# carlos_lm3886.net
KiCad netlist of a schematic drawn in EAGLE
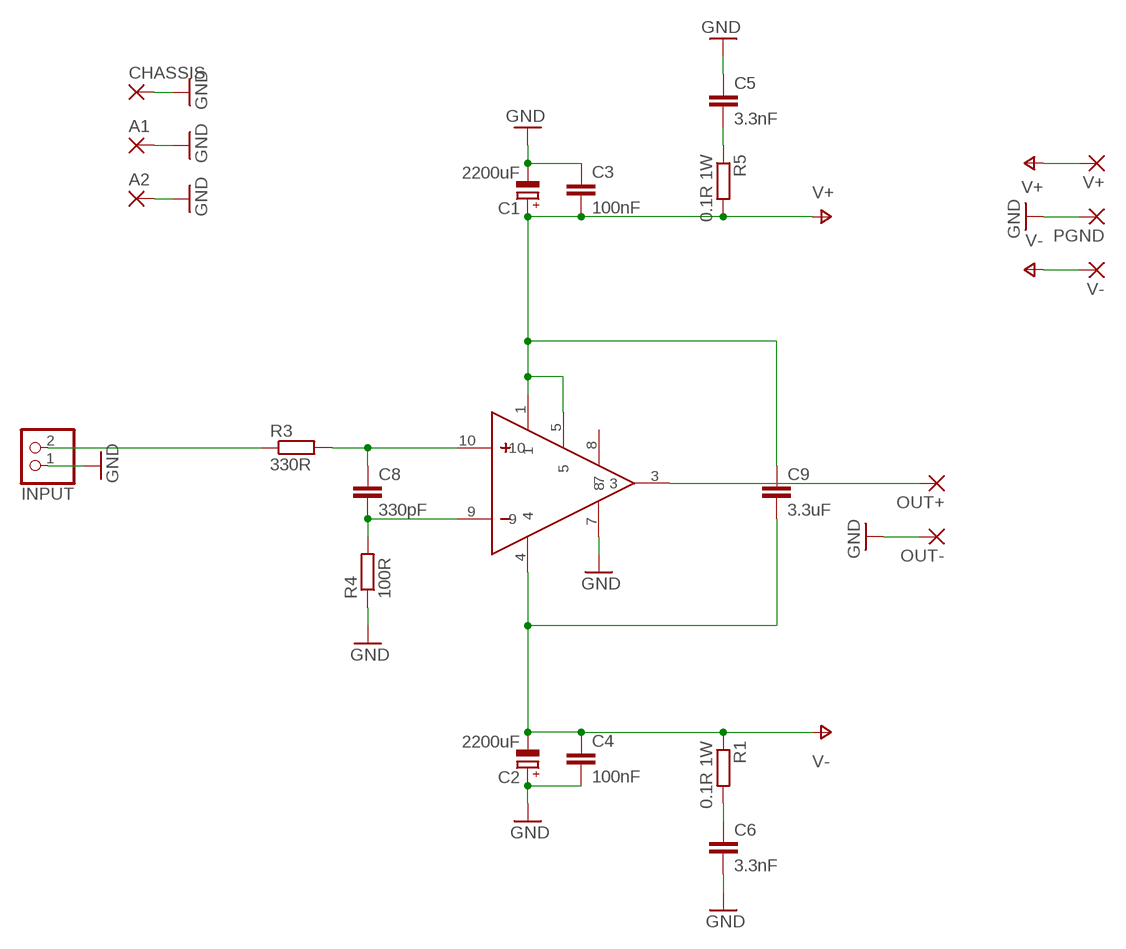
[diagram p0: schematic, sheet 1]

(export (version "E")
  (design (tool "Eeschema 10.0.6"))
  (components
    (comp (ref "A1")
      (value "2,54/1,0")
      (footprint "eagle-import:2,54_1,0")
      (libsource (lib "eagle-import") (part "2,54/1,0"))
    )
    (comp (ref "A2")
      (value "2,54/1,0")
      (footprint "eagle-import:2,54_1,0")
      (libsource (lib "eagle-import") (part "2,54/1,0"))
    )
    (comp (ref "C1")
      (value "2200uF")
      (footprint "eagle-import:E7,5-18")
      (libsource (lib "eagle-import") (part "CPOL-EUE7.5-18"))
    )
    (comp (ref "C2")
      (value "2200uF")
      (footprint "eagle-import:E7,5-18")
      (libsource (lib "eagle-import") (part "CPOL-EUE7.5-18"))
    )
    (comp (ref "C3")
      (value "100nF")
      (footprint "eagle-import:C150-054X183")
      (libsource (lib "eagle-import") (part "C-EU150-054X183"))
    )
    (comp (ref "C4")
      (value "100nF")
      (footprint "eagle-import:C150-054X183")
      (libsource (lib "eagle-import") (part "C-EU150-054X183"))
    )
    (comp (ref "C5")
      (value "3.3nF")
      (footprint "eagle-import:C075-032X103")
      (libsource (lib "eagle-import") (part "C-EU075-032X103"))
    )
    (comp (ref "C6")
      (value "3.3nF")
      (footprint "eagle-import:C075-032X103")
      (libsource (lib "eagle-import") (part "C-EU075-032X103"))
    )
    (comp (ref "C8")
      (value "330pF")
      (footprint "eagle-import:C050-045X075")
      (libsource (lib "eagle-import") (part "C-EU050-045X075"))
    )
    (comp (ref "C9")
      (value "3.3uF")
      (footprint "eagle-import:C225-087X268")
      (libsource (lib "eagle-import") (part "C-EU225-087X268"))
    )
    (comp (ref "CHASSIS")
      (value "2,54/1,0")
      (footprint "eagle-import:2,54_1,0")
      (libsource (lib "eagle-import") (part "2,54/1,0"))
    )
    (comp (ref "INPUT")
      (value "PINHD-1X2")
      (footprint "eagle-import:1X02")
      (libsource (lib "eagle-import") (part "PINHD-1X2"))
    )
    (comp (ref "OUT+")
      (value "2,54/1,0")
      (footprint "eagle-import:2,54_1,0")
      (libsource (lib "eagle-import") (part "2,54/1,0"))
    )
    (comp (ref "OUT-")
      (value "2,54/1,0")
      (footprint "eagle-import:2,54_1,0")
      (libsource (lib "eagle-import") (part "2,54/1,0"))
    )
    (comp (ref "PGND")
      (value "2,54/1,0")
      (footprint "eagle-import:2,54_1,0")
      (libsource (lib "eagle-import") (part "2,54/1,0"))
    )
    (comp (ref "R1")
      (value "0.1R 1W")
      (footprint "eagle-import:0309_10")
      (libsource (lib "eagle-import") (part "resistor_R-EU_0309/10"))
    )
    (comp (ref "R3")
      (value "330R")
      (footprint "eagle-import:0207_10")
      (libsource (lib "eagle-import") (part "R-EU_0207/10"))
    )
    (comp (ref "R4")
      (value "100R")
      (footprint "eagle-import:0207_10")
      (libsource (lib "eagle-import") (part "R-EU_0207/10"))
    )
    (comp (ref "R5")
      (value "0.1R 1W")
      (footprint "eagle-import:0309_10")
      (libsource (lib "eagle-import") (part "resistor_R-EU_0309/10"))
    )
    (comp (ref "U$1")
      (value "LM3886T")
      (footprint "eagle-import:TO220-11")
      (libsource (lib "eagle-import") (part "LM3886T"))
    )
    (comp (ref "V+")
      (value "2,54/1,0")
      (footprint "eagle-import:2,54_1,0")
      (libsource (lib "eagle-import") (part "2,54/1,0"))
    )
    (comp (ref "V-")
      (value "2,54/1,0")
      (footprint "eagle-import:2,54_1,0")
      (libsource (lib "eagle-import") (part "2,54/1,0"))
    )
  )
  (nets
    (net (code "1") (name "GND") (class "Default")
      (node (ref "A1") (pin "1") (pinfunction "P_1") (pintype "passive"))
      (node (ref "A2") (pin "1") (pinfunction "P_1") (pintype "passive"))
      (node (ref "C1") (pin "-") (pinfunction "-_-") (pintype "passive"))
      (node (ref "C2") (pin "+") (pinfunction "+_+") (pintype "passive"))
      (node (ref "C3") (pin "1") (pinfunction "1_1") (pintype "passive"))
      (node (ref "C4") (pin "2") (pinfunction "2_2") (pintype "passive"))
      (node (ref "C5") (pin "1") (pinfunction "1_1") (pintype "passive"))
      (node (ref "C6") (pin "2") (pinfunction "2_2") (pintype "passive"))
      (node (ref "CHASSIS") (pin "1") (pinfunction "P_1") (pintype "passive"))
      (node (ref "INPUT") (pin "1") (pinfunction "1_1") (pintype "passive"))
      (node (ref "OUT-") (pin "1") (pinfunction "P_1") (pintype "passive"))
      (node (ref "PGND") (pin "1") (pinfunction "P_1") (pintype "passive"))
      (node (ref "R4") (pin "1") (pinfunction "1_1") (pintype "passive"))
      (node (ref "U$1") (pin "7") (pinfunction "7_7") (pintype "power_in"))
    )
    (net (code "2") (name "Net-(C5-Pad2)") (class "Default")
      (node (ref "C5") (pin "2") (pinfunction "2_2") (pintype "passive"))
      (node (ref "R5") (pin "1") (pinfunction "1_1") (pintype "passive"))
    )
    (net (code "3") (name "Net-(C6-Pad1)") (class "Default")
      (node (ref "C6") (pin "1") (pinfunction "1_1") (pintype "passive"))
      (node (ref "R1") (pin "2") (pinfunction "2_2") (pintype "passive"))
    )
    (net (code "4") (name "Net-(C8-Pad1)") (class "Default")
      (node (ref "C8") (pin "1") (pinfunction "1_1") (pintype "passive"))
      (node (ref "R3") (pin "2") (pinfunction "2_2") (pintype "passive"))
      (node (ref "U$1") (pin "10") (pinfunction "10_10") (pintype "input"))
    )
    (net (code "5") (name "Net-(C8-Pad2)") (class "Default")
      (node (ref "C8") (pin "2") (pinfunction "2_2") (pintype "passive"))
      (node (ref "R4") (pin "2") (pinfunction "2_2") (pintype "passive"))
      (node (ref "U$1") (pin "9") (pinfunction "9_9") (pintype "input"))
    )
    (net (code "6") (name "Net-(INPUT-Pad2)") (class "Default")
      (node (ref "INPUT") (pin "2") (pinfunction "2_2") (pintype "passive"))
      (node (ref "R3") (pin "1") (pinfunction "1_1") (pintype "passive"))
    )
    (net (code "7") (name "Net-(OUT+-P)") (class "Default")
      (node (ref "OUT+") (pin "1") (pinfunction "P_1") (pintype "passive"))
      (node (ref "U$1") (pin "3") (pinfunction "3_3") (pintype "output"))
    )
    (net (code "8") (name "V+") (class "Default")
      (node (ref "C1") (pin "+") (pinfunction "+_+") (pintype "passive"))
      (node (ref "C3") (pin "2") (pinfunction "2_2") (pintype "passive"))
      (node (ref "C9") (pin "1") (pinfunction "1_1") (pintype "passive"))
      (node (ref "R5") (pin "2") (pinfunction "2_2") (pintype "passive"))
      (node (ref "U$1") (pin "1") (pinfunction "1_1") (pintype "power_in"))
      (node (ref "U$1") (pin "5") (pinfunction "5_5") (pintype "power_in"))
      (node (ref "V+") (pin "1") (pinfunction "P_1") (pintype "passive"))
    )
    (net (code "9") (name "V-") (class "Default")
      (node (ref "C2") (pin "-") (pinfunction "-_-") (pintype "passive"))
      (node (ref "C4") (pin "1") (pinfunction "1_1") (pintype "passive"))
      (node (ref "C9") (pin "2") (pinfunction "2_2") (pintype "passive"))
      (node (ref "R1") (pin "1") (pinfunction "1_1") (pintype "passive"))
      (node (ref "U$1") (pin "4") (pinfunction "4_4") (pintype "power_in"))
      (node (ref "V-") (pin "1") (pinfunction "P_1") (pintype "passive"))
    )
    (net (code "10") (name "unconnected-(U$1-Pad8)") (class "Default")
      (node (ref "U$1") (pin "8") (pinfunction "8_8") (pintype "input"))
    )
  )
)
